# mute.net
KiCad netlist of a schematic drawn in EAGLE
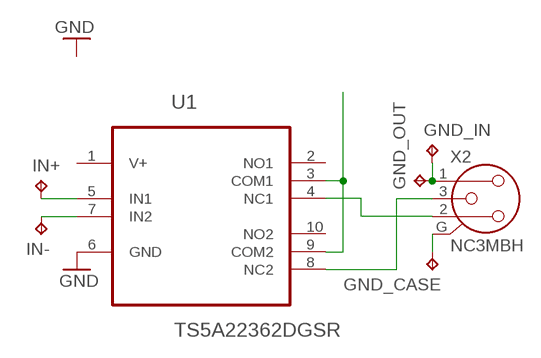
[diagram p0: schematic, sheet 1]

(export (version "E")
  (design (tool "Eeschema 10.0.6"))
  (components
    (comp (ref "GND_CASE")
      (value "TPPAD1-20")
      (footprint "eagle-import:P1-20")
      (libsource (lib "eagle-import") (part "TPPAD1-20"))
    )
    (comp (ref "GND_IN")
      (value "TPPAD1-20")
      (footprint "eagle-import:P1-20")
      (libsource (lib "eagle-import") (part "TPPAD1-20"))
    )
    (comp (ref "GND_OUT")
      (value "TPPAD1-20")
      (footprint "eagle-import:P1-20")
      (libsource (lib "eagle-import") (part "TPPAD1-20"))
    )
    (comp (ref "IN+")
      (value "TPPAD1-20")
      (footprint "eagle-import:P1-20")
      (libsource (lib "eagle-import") (part "TPPAD1-20"))
    )
    (comp (ref "IN-")
      (value "TPPAD1-20")
      (footprint "eagle-import:P1-20")
      (libsource (lib "eagle-import") (part "TPPAD1-20"))
    )
    (comp (ref "U1")
      (value "TS5A22362DGSR")
      (footprint "eagle-import:SOP50P490X110-10N")
      (libsource (lib "eagle-import") (part "TS5A22362DGSR"))
    )
    (comp (ref "X2")
      (value "NC3MBH")
      (footprint "eagle-import:NC3MBH")
      (fields (field (name "MF") "NEUTRIK"))
      (libsource (lib "eagle-import") (part "NC3MBH"))
    )
  )
  (nets
    (net (code "1") (name "/V+") (class "Default")
      (node (ref "U1") (pin "1") (pinfunction "V+_1") (pintype "power_in"))
    )
    (net (code "2") (name "GND") (class "Default")
      (node (ref "U1") (pin "6") (pinfunction "GND_6") (pintype "passive"))
    )
    (net (code "3") (name "Net-(GND_CASE-PadTP)") (class "Default")
      (node (ref "GND_CASE") (pin "TP") (pinfunction "TP_TP") (pintype "input"))
      (node (ref "X2") (pin "G") (pinfunction "G_G") (pintype "passive"))
    )
    (net (code "4") (name "Net-(GND_IN-PadTP)") (class "Default")
      (node (ref "GND_IN") (pin "TP") (pinfunction "TP_TP") (pintype "input"))
      (node (ref "GND_OUT") (pin "TP") (pinfunction "TP_TP") (pintype "input"))
      (node (ref "X2") (pin "1") (pinfunction "1_1") (pintype "passive"))
    )
    (net (code "5") (name "Net-(U1-COM1)") (class "Default")
      (node (ref "U1") (pin "3") (pinfunction "COM1_3") (pintype "passive"))
      (node (ref "U1") (pin "9") (pinfunction "COM2_9") (pintype "passive"))
    )
    (net (code "6") (name "Net-(U1-IN1)") (class "Default")
      (node (ref "IN+") (pin "TP") (pinfunction "TP_TP") (pintype "input"))
      (node (ref "U1") (pin "5") (pinfunction "IN1_5") (pintype "input"))
    )
    (net (code "7") (name "Net-(U1-IN2)") (class "Default")
      (node (ref "IN-") (pin "TP") (pinfunction "TP_TP") (pintype "input"))
      (node (ref "U1") (pin "7") (pinfunction "IN2_7") (pintype "input"))
    )
    (net (code "8") (name "Net-(U1-NC1)") (class "Default")
      (node (ref "U1") (pin "4") (pinfunction "NC1_4") (pintype "passive"))
      (node (ref "X2") (pin "2") (pinfunction "2_2") (pintype "passive"))
    )
    (net (code "9") (name "Net-(U1-NC2)") (class "Default")
      (node (ref "U1") (pin "8") (pinfunction "NC2_8") (pintype "passive"))
      (node (ref "X2") (pin "3") (pinfunction "3_3") (pintype "passive"))
    )
    (net (code "10") (name "unconnected-(U1-NO1-Pad2)") (class "Default")
      (node (ref "U1") (pin "2") (pinfunction "NO1_2") (pintype "passive"))
    )
    (net (code "11") (name "unconnected-(U1-NO2-Pad10)") (class "Default")
      (node (ref "U1") (pin "10") (pinfunction "NO2_10") (pintype "passive"))
    )
  )
)
